# ADC.net
KiCad netlist of a schematic drawn in Altium Designer
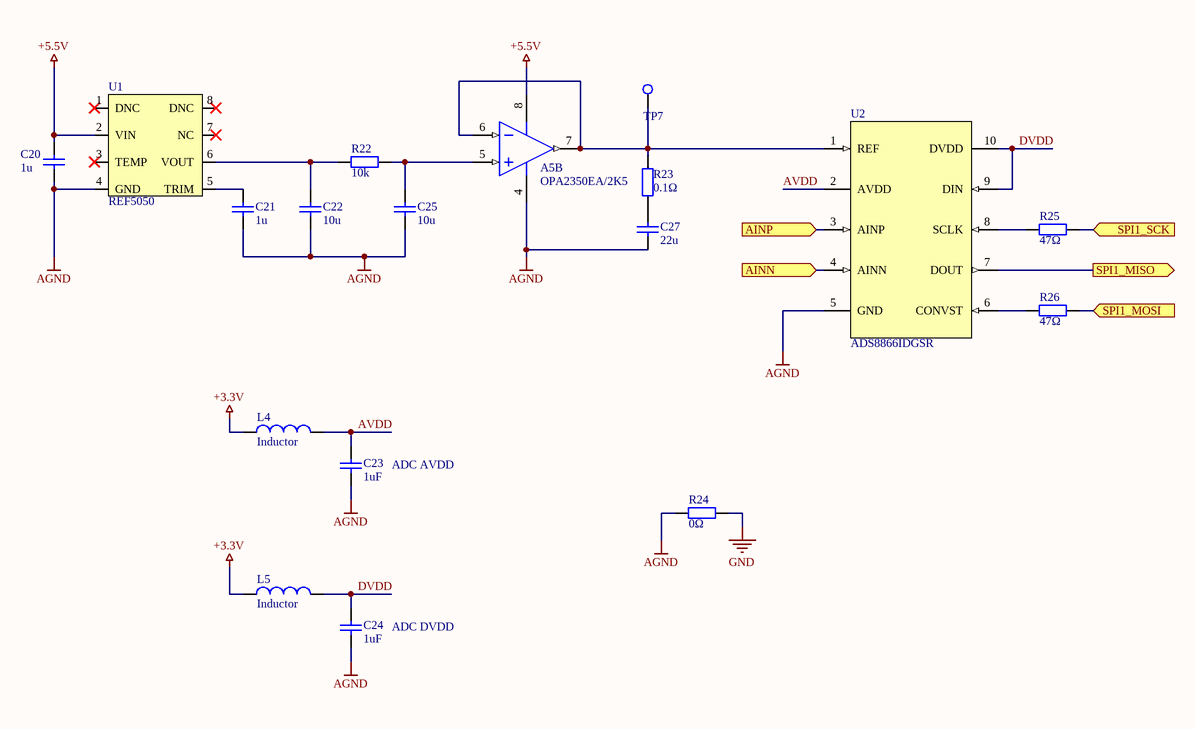
[diagram p0: ADC.SchDoc]

(export (version "E")
  (design (tool "Eeschema 10.0.6"))
  (components
    (comp (ref "A5")
      (value "OPA2350EA/2K5")
      (footprint "SOIC127P600X175-8N")
      (libsource (lib "TI Amplifiers and Linear Operational Amplifier Precision Amplifier Part One") (part "OPA2350EA/250"))
    )
    (comp (ref "C20")
      (value "1u")
      (footprint "CAPC1608X87N")
      (libsource (lib "Miscellaneous Devices") (part "Cap"))
    )
    (comp (ref "C21")
      (value "1u")
      (footprint "CAPC1608X87N")
      (libsource (lib "Miscellaneous Devices") (part "Cap"))
    )
    (comp (ref "C22")
      (value "10u")
      (footprint "CAPC2012X110N")
      (libsource (lib "Miscellaneous Devices") (part "Cap"))
    )
    (comp (ref "C23")
      (value "1uF")
      (footprint "CAPC1608X87N")
      (libsource (lib "Miscellaneous Devices") (part "Cap"))
    )
    (comp (ref "C24")
      (value "1uF")
      (footprint "CAPC1608X87N")
      (libsource (lib "Miscellaneous Devices") (part "Cap"))
    )
    (comp (ref "C25")
      (value "10u")
      (footprint "CAPC2012X110N")
      (libsource (lib "Miscellaneous Devices") (part "Cap"))
    )
    (comp (ref "C27")
      (value "22u")
      (footprint "CAPC2012X110N")
      (libsource (lib "Miscellaneous Devices") (part "Cap"))
    )
    (comp (ref "L4")
      (value "Inductor")
      (footprint "RESC1608X55N")
      (libsource (lib "Miscellaneous Devices") (part "Inductor"))
    )
    (comp (ref "L5")
      (value "Inductor")
      (footprint "INDC1608L")
      (libsource (lib "Miscellaneous Devices") (part "Inductor"))
    )
    (comp (ref "R22")
      (value "10k")
      (footprint "RESC1608X55N")
      (fields (field (name "MOUSER PART NUMBER") "603-RC0603FR-0710KL"))
      (libsource (lib "Miscellaneous Devices") (part "Res2"))
    )
    (comp (ref "R23") (value "0.1Ω") (footprint "RESC1608X55N") (libsource (lib "") (part "Res2_1")))
    (comp (ref "R24")
      (value "0Ω")
      (footprint "RESC1608X55N")
      (libsource (lib "Miscellaneous Devices") (part "Res2"))
    )
    (comp (ref "R25")
      (value "47Ω")
      (footprint "RESC1608X55N")
      (libsource (lib "Miscellaneous Devices") (part "Res2"))
    )
    (comp (ref "R26")
      (value "47Ω")
      (footprint "RESC1608X55N")
      (libsource (lib "Miscellaneous Devices") (part "Res2"))
    )
    (comp (ref "TP7")
      (value "TP")
      (footprint "TEST-POINT")
      (description "Generic test point")
      (libsource (lib "Custom_Lib") (part "TEST_POINT"))
    )
    (comp (ref "U1")
      (value "REF5050")
      (footprint "SOIC127P600X175-8N")
      (libsource (lib "Custom_Lib") (part "REF5050"))
    )
    (comp (ref "U2")
      (value "ADS8866IDGSR")
      (footprint "SOP50P490X110-10N")
      (libsource (lib "Custom_Lib") (part "AD8866"))
    )
  )
  (nets
    (net (code "1") (name "+3.3V") (class "Default")
      (node (ref "L4") (pin "1") (pinfunction "1_1") (pintype "passive"))
      (node (ref "L5") (pin "1") (pinfunction "1_1") (pintype "passive"))
    )
    (net (code "2") (name "+5.5V") (class "Default")
      (node (ref "A5") (pin "8") (pinfunction "V+_8") (pintype "power_in"))
      (node (ref "C20") (pin "2") (pinfunction "2_2") (pintype "passive"))
      (node (ref "U1") (pin "2") (pinfunction "VIN_2") (pintype "passive"))
    )
    (net (code "3") (name "/AINN") (class "Default")
      (node (ref "U2") (pin "4") (pinfunction "AINN_4") (pintype "input"))
    )
    (net (code "4") (name "/AINP") (class "Default")
      (node (ref "U2") (pin "3") (pinfunction "AINP_3") (pintype "input"))
    )
    (net (code "5") (name "/AVDD") (class "Default")
      (node (ref "C23") (pin "2") (pinfunction "2_2") (pintype "passive"))
      (node (ref "L4") (pin "2") (pinfunction "2_2") (pintype "passive"))
      (node (ref "U2") (pin "2") (pinfunction "AVDD_2") (pintype "power_in"))
    )
    (net (code "6") (name "/DVDD") (class "Default")
      (node (ref "C24") (pin "2") (pinfunction "2_2") (pintype "passive"))
      (node (ref "L5") (pin "2") (pinfunction "2_2") (pintype "passive"))
      (node (ref "U2") (pin "10") (pinfunction "DVDD_10") (pintype "power_in"))
      (node (ref "U2") (pin "9") (pinfunction "DIN_9") (pintype "input"))
    )
    (net (code "7") (name "/SPI1_MISO") (class "Default")
      (node (ref "U2") (pin "7") (pinfunction "DOUT_7") (pintype "output"))
    )
    (net (code "8") (name "/SPI1_MOSI") (class "Default")
      (node (ref "R26") (pin "2") (pinfunction "2_2") (pintype "passive"))
    )
    (net (code "9") (name "/SPI1_SCK") (class "Default")
      (node (ref "R25") (pin "2") (pinfunction "2_2") (pintype "passive"))
    )
    (net (code "10") (name "AGND") (class "Default")
      (node (ref "A5") (pin "4") (pinfunction "V-_4") (pintype "power_in"))
      (node (ref "C20") (pin "1") (pinfunction "1_1") (pintype "passive"))
      (node (ref "C21") (pin "1") (pinfunction "1_1") (pintype "passive"))
      (node (ref "C22") (pin "1") (pinfunction "1_1") (pintype "passive"))
      (node (ref "C23") (pin "1") (pinfunction "1_1") (pintype "passive"))
      (node (ref "C24") (pin "1") (pinfunction "1_1") (pintype "passive"))
      (node (ref "C25") (pin "1") (pinfunction "1_1") (pintype "passive"))
      (node (ref "C27") (pin "2") (pinfunction "2_2") (pintype "passive"))
      (node (ref "R24") (pin "1") (pinfunction "1_1") (pintype "passive"))
      (node (ref "U1") (pin "4") (pinfunction "GND_4") (pintype "passive"))
      (node (ref "U2") (pin "5") (pinfunction "GND_5") (pintype "power_in"))
    )
    (net (code "11") (name "GND") (class "Default")
      (node (ref "R24") (pin "2") (pinfunction "2_2") (pintype "passive"))
    )
    (net (code "12") (name "Net-(A5B-IN_B+)") (class "Default")
      (node (ref "A5") (pin "5") (pinfunction "IN_B+_5") (pintype "input"))
      (node (ref "C25") (pin "2") (pinfunction "2_2") (pintype "passive"))
      (node (ref "R22") (pin "2") (pinfunction "2_2") (pintype "passive"))
    )
    (net (code "13") (name "Net-(A5B-IN_B-)") (class "Default")
      (node (ref "A5") (pin "6") (pinfunction "IN_B-_6") (pintype "input"))
      (node (ref "A5") (pin "7") (pinfunction "OUT_B_7") (pintype "output"))
      (node (ref "R23") (pin "2") (pinfunction "2_2") (pintype "passive"))
      (node (ref "TP7") (pin "0") (pinfunction "0_0") (pintype "passive"))
      (node (ref "U2") (pin "1") (pinfunction "REF_1") (pintype "input"))
    )
    (net (code "14") (name "Net-(C27-Pad1)") (class "Default")
      (node (ref "C27") (pin "1") (pinfunction "1_1") (pintype "passive"))
      (node (ref "R23") (pin "1") (pinfunction "1_1") (pintype "passive"))
    )
    (net (code "15") (name "Net-(U1-TRIM)") (class "Default")
      (node (ref "C21") (pin "2") (pinfunction "2_2") (pintype "passive"))
      (node (ref "U1") (pin "5") (pinfunction "TRIM_5") (pintype "passive"))
    )
    (net (code "16") (name "Net-(U1-VOUT)") (class "Default")
      (node (ref "C22") (pin "2") (pinfunction "2_2") (pintype "passive"))
      (node (ref "R22") (pin "1") (pinfunction "1_1") (pintype "passive"))
      (node (ref "U1") (pin "6") (pinfunction "VOUT_6") (pintype "passive"))
    )
    (net (code "17") (name "Net-(U2-CONVST)") (class "Default")
      (node (ref "R26") (pin "1") (pinfunction "1_1") (pintype "passive"))
      (node (ref "U2") (pin "6") (pinfunction "CONVST_6") (pintype "input"))
    )
    (net (code "18") (name "Net-(U2-SCLK)") (class "Default")
      (node (ref "R25") (pin "1") (pinfunction "1_1") (pintype "passive"))
      (node (ref "U2") (pin "8") (pinfunction "SCLK_8") (pintype "input"))
    )
    (net (code "19") (name "unconnected-(U1-DNC-Pad1)") (class "Default")
      (node (ref "U1") (pin "1") (pinfunction "DNC_1") (pintype "passive+no_connect"))
    )
    (net (code "20") (name "unconnected-(U1-DNC-Pad8)") (class "Default")
      (node (ref "U1") (pin "8") (pinfunction "DNC_8") (pintype "passive+no_connect"))
    )
    (net (code "21") (name "unconnected-(U1-NC-Pad7)") (class "Default")
      (node (ref "U1") (pin "7") (pinfunction "NC_7") (pintype "passive+no_connect"))
    )
    (net (code "22") (name "unconnected-(U1-TEMP-Pad3)") (class "Default")
      (node (ref "U1") (pin "3") (pinfunction "TEMP_3") (pintype "passive+no_connect"))
    )
  )
)
